# BarGraph.net
KiCad netlist of a schematic drawn in Altium Designer
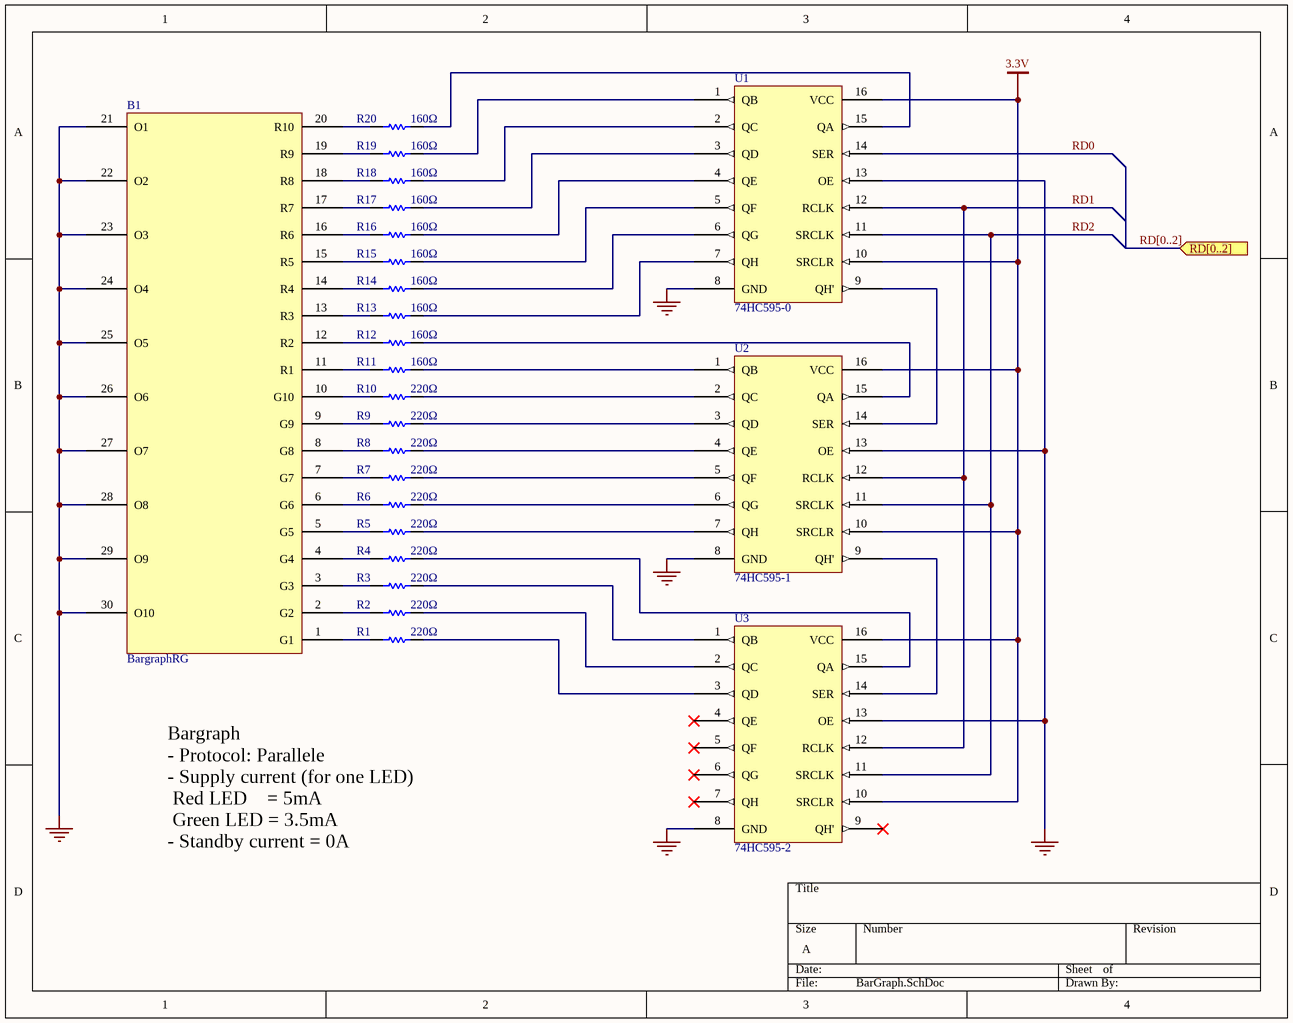
[diagram p0: BarGraph.SchDoc]

(export (version "E")
  (design (tool "Eeschema 10.0.6"))
  (components
    (comp (ref "B1")
      (value "BargraphRG")
      (footprint "BargraphRG")
      (description "Bargraph")
      (fields (field (name "MANUFACTURER") "KINGBRIGHT"))
      (libsource (lib "Electroplant") (part "BargraphRG"))
    )
    (comp (ref "R1")
      (value "220Ω")
      (footprint "R0603")
      (description "Resistor")
      (fields (field (name "MANUFACTURER") "MULTICOMP") (field (name "PUBLISHER") "Altium Limited"))
      (libsource (lib "Miscellaneous Devices") (part "Res1"))
    )
    (comp (ref "R2")
      (value "220Ω")
      (footprint "R0603")
      (description "Resistor")
      (fields (field (name "MANUFACTURER") "MULTICOMP") (field (name "PUBLISHER") "Altium Limited"))
      (libsource (lib "Miscellaneous Devices") (part "Res1"))
    )
    (comp (ref "R3")
      (value "220Ω")
      (footprint "R0603")
      (description "Resistor")
      (fields (field (name "MANUFACTURER") "MULTICOMP") (field (name "PUBLISHER") "Altium Limited"))
      (libsource (lib "Miscellaneous Devices") (part "Res1"))
    )
    (comp (ref "R4")
      (value "220Ω")
      (footprint "R0603")
      (description "Resistor")
      (fields (field (name "MANUFACTURER") "MULTICOMP") (field (name "PUBLISHER") "Altium Limited"))
      (libsource (lib "Miscellaneous Devices") (part "Res1"))
    )
    (comp (ref "R5")
      (value "220Ω")
      (footprint "R0603")
      (description "Resistor")
      (fields (field (name "MANUFACTURER") "MULTICOMP") (field (name "PUBLISHER") "Altium Limited"))
      (libsource (lib "Miscellaneous Devices") (part "Res1"))
    )
    (comp (ref "R6")
      (value "220Ω")
      (footprint "R0603")
      (description "Resistor")
      (fields (field (name "MANUFACTURER") "MULTICOMP") (field (name "PUBLISHER") "Altium Limited"))
      (libsource (lib "Miscellaneous Devices") (part "Res1"))
    )
    (comp (ref "R7")
      (value "220Ω")
      (footprint "R0603")
      (description "Resistor")
      (fields (field (name "MANUFACTURER") "MULTICOMP") (field (name "PUBLISHER") "Altium Limited"))
      (libsource (lib "Miscellaneous Devices") (part "Res1"))
    )
    (comp (ref "R8")
      (value "220Ω")
      (footprint "R0603")
      (description "Resistor")
      (fields (field (name "MANUFACTURER") "MULTICOMP") (field (name "PUBLISHER") "Altium Limited"))
      (libsource (lib "Miscellaneous Devices") (part "Res1"))
    )
    (comp (ref "R9")
      (value "220Ω")
      (footprint "R0603")
      (description "Resistor")
      (fields (field (name "MANUFACTURER") "MULTICOMP") (field (name "PUBLISHER") "Altium Limited"))
      (libsource (lib "Miscellaneous Devices") (part "Res1"))
    )
    (comp (ref "R10")
      (value "220Ω")
      (footprint "R0603")
      (description "Resistor")
      (fields (field (name "MANUFACTURER") "MULTICOMP") (field (name "PUBLISHER") "Altium Limited"))
      (libsource (lib "Miscellaneous Devices") (part "Res1"))
    )
    (comp (ref "R11")
      (value "160Ω")
      (footprint "R0603")
      (description "Resistor")
      (fields (field (name "MANUFACTURER") "MULTICOMP") (field (name "PUBLISHER") "Altium Limited"))
      (libsource (lib "Miscellaneous Devices") (part "Res1"))
    )
    (comp (ref "R12")
      (value "160Ω")
      (footprint "R0603")
      (description "Resistor")
      (fields (field (name "MANUFACTURER") "MULTICOMP") (field (name "PUBLISHER") "Altium Limited"))
      (libsource (lib "Miscellaneous Devices") (part "Res1"))
    )
    (comp (ref "R13")
      (value "160Ω")
      (footprint "R0603")
      (description "Resistor")
      (fields (field (name "MANUFACTURER") "MULTICOMP") (field (name "PUBLISHER") "Altium Limited"))
      (libsource (lib "Miscellaneous Devices") (part "Res1"))
    )
    (comp (ref "R14")
      (value "160Ω")
      (footprint "R0603")
      (description "Resistor")
      (fields (field (name "MANUFACTURER") "MULTICOMP") (field (name "PUBLISHER") "Altium Limited"))
      (libsource (lib "Miscellaneous Devices") (part "Res1"))
    )
    (comp (ref "R15")
      (value "160Ω")
      (footprint "R0603")
      (description "Resistor")
      (fields (field (name "MANUFACTURER") "MULTICOMP") (field (name "PUBLISHER") "Altium Limited"))
      (libsource (lib "Miscellaneous Devices") (part "Res1"))
    )
    (comp (ref "R16")
      (value "160Ω")
      (footprint "R0603")
      (description "Resistor")
      (fields (field (name "MANUFACTURER") "MULTICOMP") (field (name "PUBLISHER") "Altium Limited"))
      (libsource (lib "Miscellaneous Devices") (part "Res1"))
    )
    (comp (ref "R17")
      (value "160Ω")
      (footprint "R0603")
      (description "Resistor")
      (fields (field (name "MANUFACTURER") "MULTICOMP") (field (name "PUBLISHER") "Altium Limited"))
      (libsource (lib "Miscellaneous Devices") (part "Res1"))
    )
    (comp (ref "R18")
      (value "160Ω")
      (footprint "R0603")
      (description "Resistor")
      (fields (field (name "MANUFACTURER") "MULTICOMP") (field (name "PUBLISHER") "Altium Limited"))
      (libsource (lib "Miscellaneous Devices") (part "Res1"))
    )
    (comp (ref "R19")
      (value "160Ω")
      (footprint "R0603")
      (description "Resistor")
      (fields (field (name "MANUFACTURER") "MULTICOMP") (field (name "PUBLISHER") "Altium Limited"))
      (libsource (lib "Miscellaneous Devices") (part "Res1"))
    )
    (comp (ref "R20")
      (value "160Ω")
      (footprint "R0603")
      (description "Resistor")
      (fields (field (name "MANUFACTURER") "MULTICOMP") (field (name "PUBLISHER") "Altium Limited"))
      (libsource (lib "Miscellaneous Devices") (part "Res1"))
    )
    (comp (ref "U1")
      (value "74HC595-0")
      (footprint "SN74HC595D")
      (description "ShiftRegister")
      (fields (field (name "MANUFACTURER") "TEXAS INSTRUMENTS"))
      (libsource (lib "Electroplant") (part "74HC595"))
    )
    (comp (ref "U2")
      (value "74HC595-1")
      (footprint "SN74HC595D")
      (description "ShiftRegister")
      (fields (field (name "MANUFACTURER") "TEXAS INSTRUMENTS"))
      (libsource (lib "Electroplant") (part "74HC595"))
    )
    (comp (ref "U3")
      (value "74HC595-2")
      (footprint "SN74HC595D")
      (description "ShiftRegister")
      (fields (field (name "MANUFACTURER") "TEXAS INSTRUMENTS"))
      (libsource (lib "Electroplant") (part "74HC595"))
    )
  )
  (nets
    (net (code "1") (name "/RD0") (class "Default")
      (node (ref "U1") (pin "14") (pinfunction "SER_14") (pintype "input"))
    )
    (net (code "2") (name "/RD1") (class "Default")
      (node (ref "U1") (pin "12") (pinfunction "RCLK_12") (pintype "input"))
      (node (ref "U2") (pin "12") (pinfunction "RCLK_12") (pintype "input"))
      (node (ref "U3") (pin "12") (pinfunction "RCLK_12") (pintype "input"))
    )
    (net (code "3") (name "/RD2") (class "Default")
      (node (ref "U1") (pin "11") (pinfunction "SRCLK_11") (pintype "input"))
      (node (ref "U2") (pin "11") (pinfunction "SRCLK_11") (pintype "input"))
      (node (ref "U3") (pin "11") (pinfunction "SRCLK_11") (pintype "input"))
    )
    (net (code "5") (name "3.3V") (class "Default")
      (node (ref "U1") (pin "10") (pinfunction "SRCLR_10") (pintype "input"))
      (node (ref "U1") (pin "16") (pinfunction "VCC_16") (pintype "power_in"))
      (node (ref "U2") (pin "10") (pinfunction "SRCLR_10") (pintype "input"))
      (node (ref "U2") (pin "16") (pinfunction "VCC_16") (pintype "power_in"))
      (node (ref "U3") (pin "10") (pinfunction "SRCLR_10") (pintype "input"))
      (node (ref "U3") (pin "16") (pinfunction "VCC_16") (pintype "power_in"))
    )
    (net (code "6") (name "GND") (class "Default")
      (node (ref "B1") (pin "21") (pinfunction "O1_21") (pintype "power_in"))
      (node (ref "B1") (pin "22") (pinfunction "O2_22") (pintype "power_in"))
      (node (ref "B1") (pin "23") (pinfunction "O3_23") (pintype "power_in"))
      (node (ref "B1") (pin "24") (pinfunction "O4_24") (pintype "power_in"))
      (node (ref "B1") (pin "25") (pinfunction "O5_25") (pintype "power_in"))
      (node (ref "B1") (pin "26") (pinfunction "O6_26") (pintype "power_in"))
      (node (ref "B1") (pin "27") (pinfunction "O7_27") (pintype "power_in"))
      (node (ref "B1") (pin "28") (pinfunction "O8_28") (pintype "power_in"))
      (node (ref "B1") (pin "29") (pinfunction "O9_29") (pintype "power_in"))
      (node (ref "B1") (pin "30") (pinfunction "O10_30") (pintype "power_in"))
      (node (ref "U1") (pin "13") (pinfunction "OE_13") (pintype "input"))
      (node (ref "U1") (pin "8") (pinfunction "GND_8") (pintype "power_in"))
      (node (ref "U2") (pin "13") (pinfunction "OE_13") (pintype "input"))
      (node (ref "U2") (pin "8") (pinfunction "GND_8") (pintype "power_in"))
      (node (ref "U3") (pin "13") (pinfunction "OE_13") (pintype "input"))
      (node (ref "U3") (pin "8") (pinfunction "GND_8") (pintype "power_in"))
    )
    (net (code "7") (name "Net-(B1-G1)") (class "Default")
      (node (ref "B1") (pin "1") (pinfunction "G1_1") (pintype "power_in"))
      (node (ref "R1") (pin "1") (pinfunction "1_1") (pintype "passive"))
    )
    (net (code "8") (name "Net-(B1-G2)") (class "Default")
      (node (ref "B1") (pin "2") (pinfunction "G2_2") (pintype "power_in"))
      (node (ref "R2") (pin "1") (pinfunction "1_1") (pintype "passive"))
    )
    (net (code "9") (name "Net-(B1-G3)") (class "Default")
      (node (ref "B1") (pin "3") (pinfunction "G3_3") (pintype "power_in"))
      (node (ref "R3") (pin "1") (pinfunction "1_1") (pintype "passive"))
    )
    (net (code "10") (name "Net-(B1-G4)") (class "Default")
      (node (ref "B1") (pin "4") (pinfunction "G4_4") (pintype "power_in"))
      (node (ref "R4") (pin "1") (pinfunction "1_1") (pintype "passive"))
    )
    (net (code "11") (name "Net-(B1-G5)") (class "Default")
      (node (ref "B1") (pin "5") (pinfunction "G5_5") (pintype "power_in"))
      (node (ref "R5") (pin "1") (pinfunction "1_1") (pintype "passive"))
    )
    (net (code "12") (name "Net-(B1-G6)") (class "Default")
      (node (ref "B1") (pin "6") (pinfunction "G6_6") (pintype "power_in"))
      (node (ref "R6") (pin "1") (pinfunction "1_1") (pintype "passive"))
    )
    (net (code "13") (name "Net-(B1-G7)") (class "Default")
      (node (ref "B1") (pin "7") (pinfunction "G7_7") (pintype "power_in"))
      (node (ref "R7") (pin "1") (pinfunction "1_1") (pintype "passive"))
    )
    (net (code "14") (name "Net-(B1-G8)") (class "Default")
      (node (ref "B1") (pin "8") (pinfunction "G8_8") (pintype "power_in"))
      (node (ref "R8") (pin "1") (pinfunction "1_1") (pintype "passive"))
    )
    (net (code "15") (name "Net-(B1-G9)") (class "Default")
      (node (ref "B1") (pin "9") (pinfunction "G9_9") (pintype "power_in"))
      (node (ref "R9") (pin "1") (pinfunction "1_1") (pintype "passive"))
    )
    (net (code "16") (name "Net-(B1-G10)") (class "Default")
      (node (ref "B1") (pin "10") (pinfunction "G10_10") (pintype "power_in"))
      (node (ref "R10") (pin "1") (pinfunction "1_1") (pintype "passive"))
    )
    (net (code "17") (name "Net-(B1-R1)") (class "Default")
      (node (ref "B1") (pin "11") (pinfunction "R1_11") (pintype "power_in"))
      (node (ref "R11") (pin "1") (pinfunction "1_1") (pintype "passive"))
    )
    (net (code "18") (name "Net-(B1-R2)") (class "Default")
      (node (ref "B1") (pin "12") (pinfunction "R2_12") (pintype "power_in"))
      (node (ref "R12") (pin "1") (pinfunction "1_1") (pintype "passive"))
    )
    (net (code "19") (name "Net-(B1-R3)") (class "Default")
      (node (ref "B1") (pin "13") (pinfunction "R3_13") (pintype "power_in"))
      (node (ref "R13") (pin "1") (pinfunction "1_1") (pintype "passive"))
    )
    (net (code "20") (name "Net-(B1-R4)") (class "Default")
      (node (ref "B1") (pin "14") (pinfunction "R4_14") (pintype "power_in"))
      (node (ref "R14") (pin "1") (pinfunction "1_1") (pintype "passive"))
    )
    (net (code "21") (name "Net-(B1-R5)") (class "Default")
      (node (ref "B1") (pin "15") (pinfunction "R5_15") (pintype "power_in"))
      (node (ref "R15") (pin "1") (pinfunction "1_1") (pintype "passive"))
    )
    (net (code "22") (name "Net-(B1-R6)") (class "Default")
      (node (ref "B1") (pin "16") (pinfunction "R6_16") (pintype "power_in"))
      (node (ref "R16") (pin "1") (pinfunction "1_1") (pintype "passive"))
    )
    (net (code "23") (name "Net-(B1-R7)") (class "Default")
      (node (ref "B1") (pin "17") (pinfunction "R7_17") (pintype "power_in"))
      (node (ref "R17") (pin "1") (pinfunction "1_1") (pintype "passive"))
    )
    (net (code "24") (name "Net-(B1-R8)") (class "Default")
      (node (ref "B1") (pin "18") (pinfunction "R8_18") (pintype "power_in"))
      (node (ref "R18") (pin "1") (pinfunction "1_1") (pintype "passive"))
    )
    (net (code "25") (name "Net-(B1-R9)") (class "Default")
      (node (ref "B1") (pin "19") (pinfunction "R9_19") (pintype "power_in"))
      (node (ref "R19") (pin "1") (pinfunction "1_1") (pintype "passive"))
    )
    (net (code "26") (name "Net-(B1-R10)") (class "Default")
      (node (ref "B1") (pin "20") (pinfunction "R10_20") (pintype "power_in"))
      (node (ref "R20") (pin "1") (pinfunction "1_1") (pintype "passive"))
    )
    (net (code "27") (name "Net-(U1-QA)") (class "Default")
      (node (ref "R20") (pin "2") (pinfunction "2_2") (pintype "passive"))
      (node (ref "U1") (pin "15") (pinfunction "QA_15") (pintype "output"))
    )
    (net (code "28") (name "Net-(U1-QB)") (class "Default")
      (node (ref "R19") (pin "2") (pinfunction "2_2") (pintype "passive"))
      (node (ref "U1") (pin "1") (pinfunction "QB_1") (pintype "output"))
    )
    (net (code "29") (name "Net-(U1-QC)") (class "Default")
      (node (ref "R18") (pin "2") (pinfunction "2_2") (pintype "passive"))
      (node (ref "U1") (pin "2") (pinfunction "QC_2") (pintype "output"))
    )
    (net (code "30") (name "Net-(U1-QD)") (class "Default")
      (node (ref "R17") (pin "2") (pinfunction "2_2") (pintype "passive"))
      (node (ref "U1") (pin "3") (pinfunction "QD_3") (pintype "output"))
    )
    (net (code "31") (name "Net-(U1-QE)") (class "Default")
      (node (ref "R16") (pin "2") (pinfunction "2_2") (pintype "passive"))
      (node (ref "U1") (pin "4") (pinfunction "QE_4") (pintype "output"))
    )
    (net (code "32") (name "Net-(U1-QF)") (class "Default")
      (node (ref "R15") (pin "2") (pinfunction "2_2") (pintype "passive"))
      (node (ref "U1") (pin "5") (pinfunction "QF_5") (pintype "output"))
    )
    (net (code "33") (name "Net-(U1-QG)") (class "Default")
      (node (ref "R14") (pin "2") (pinfunction "2_2") (pintype "passive"))
      (node (ref "U1") (pin "6") (pinfunction "QG_6") (pintype "output"))
    )
    (net (code "34") (name "Net-(U1-QH')") (class "Default")
      (node (ref "U1") (pin "9") (pinfunction "QH'_9") (pintype "output"))
      (node (ref "U2") (pin "14") (pinfunction "SER_14") (pintype "input"))
    )
    (net (code "35") (name "Net-(U1-QH)") (class "Default")
      (node (ref "R13") (pin "2") (pinfunction "2_2") (pintype "passive"))
      (node (ref "U1") (pin "7") (pinfunction "QH_7") (pintype "output"))
    )
    (net (code "36") (name "Net-(U2-QA)") (class "Default")
      (node (ref "R12") (pin "2") (pinfunction "2_2") (pintype "passive"))
      (node (ref "U2") (pin "15") (pinfunction "QA_15") (pintype "output"))
    )
    (net (code "37") (name "Net-(U2-QB)") (class "Default")
      (node (ref "R11") (pin "2") (pinfunction "2_2") (pintype "passive"))
      (node (ref "U2") (pin "1") (pinfunction "QB_1") (pintype "output"))
    )
    (net (code "38") (name "Net-(U2-QC)") (class "Default")
      (node (ref "R10") (pin "2") (pinfunction "2_2") (pintype "passive"))
      (node (ref "U2") (pin "2") (pinfunction "QC_2") (pintype "output"))
    )
    (net (code "39") (name "Net-(U2-QD)") (class "Default")
      (node (ref "R9") (pin "2") (pinfunction "2_2") (pintype "passive"))
      (node (ref "U2") (pin "3") (pinfunction "QD_3") (pintype "output"))
    )
    (net (code "40") (name "Net-(U2-QE)") (class "Default")
      (node (ref "R8") (pin "2") (pinfunction "2_2") (pintype "passive"))
      (node (ref "U2") (pin "4") (pinfunction "QE_4") (pintype "output"))
    )
    (net (code "41") (name "Net-(U2-QF)") (class "Default")
      (node (ref "R7") (pin "2") (pinfunction "2_2") (pintype "passive"))
      (node (ref "U2") (pin "5") (pinfunction "QF_5") (pintype "output"))
    )
    (net (code "42") (name "Net-(U2-QG)") (class "Default")
      (node (ref "R6") (pin "2") (pinfunction "2_2") (pintype "passive"))
      (node (ref "U2") (pin "6") (pinfunction "QG_6") (pintype "output"))
    )
    (net (code "43") (name "Net-(U2-QH')") (class "Default")
      (node (ref "U2") (pin "9") (pinfunction "QH'_9") (pintype "output"))
      (node (ref "U3") (pin "14") (pinfunction "SER_14") (pintype "input"))
    )
    (net (code "44") (name "Net-(U2-QH)") (class "Default")
      (node (ref "R5") (pin "2") (pinfunction "2_2") (pintype "passive"))
      (node (ref "U2") (pin "7") (pinfunction "QH_7") (pintype "output"))
    )
    (net (code "45") (name "Net-(U3-QA)") (class "Default")
      (node (ref "R4") (pin "2") (pinfunction "2_2") (pintype "passive"))
      (node (ref "U3") (pin "15") (pinfunction "QA_15") (pintype "output"))
    )
    (net (code "46") (name "Net-(U3-QB)") (class "Default")
      (node (ref "R3") (pin "2") (pinfunction "2_2") (pintype "passive"))
      (node (ref "U3") (pin "1") (pinfunction "QB_1") (pintype "output"))
    )
    (net (code "47") (name "Net-(U3-QC)") (class "Default")
      (node (ref "R2") (pin "2") (pinfunction "2_2") (pintype "passive"))
      (node (ref "U3") (pin "2") (pinfunction "QC_2") (pintype "output"))
    )
    (net (code "48") (name "Net-(U3-QD)") (class "Default")
      (node (ref "R1") (pin "2") (pinfunction "2_2") (pintype "passive"))
      (node (ref "U3") (pin "3") (pinfunction "QD_3") (pintype "output"))
    )
    (net (code "49") (name "unconnected-(U3-QE-Pad4)") (class "Default")
      (node (ref "U3") (pin "4") (pinfunction "QE_4") (pintype "output+no_connect"))
    )
    (net (code "50") (name "unconnected-(U3-QF-Pad5)") (class "Default")
      (node (ref "U3") (pin "5") (pinfunction "QF_5") (pintype "output+no_connect"))
    )
    (net (code "51") (name "unconnected-(U3-QG-Pad6)") (class "Default")
      (node (ref "U3") (pin "6") (pinfunction "QG_6") (pintype "output+no_connect"))
    )
    (net (code "52") (name "unconnected-(U3-QH'-Pad9)") (class "Default")
      (node (ref "U3") (pin "9") (pinfunction "QH'_9") (pintype "output+no_connect"))
    )
    (net (code "53") (name "unconnected-(U3-QH-Pad7)") (class "Default")
      (node (ref "U3") (pin "7") (pinfunction "QH_7") (pintype "output+no_connect"))
    )
  )
)
